# phase.net
KiCad netlist of a schematic drawn in Altium Designer
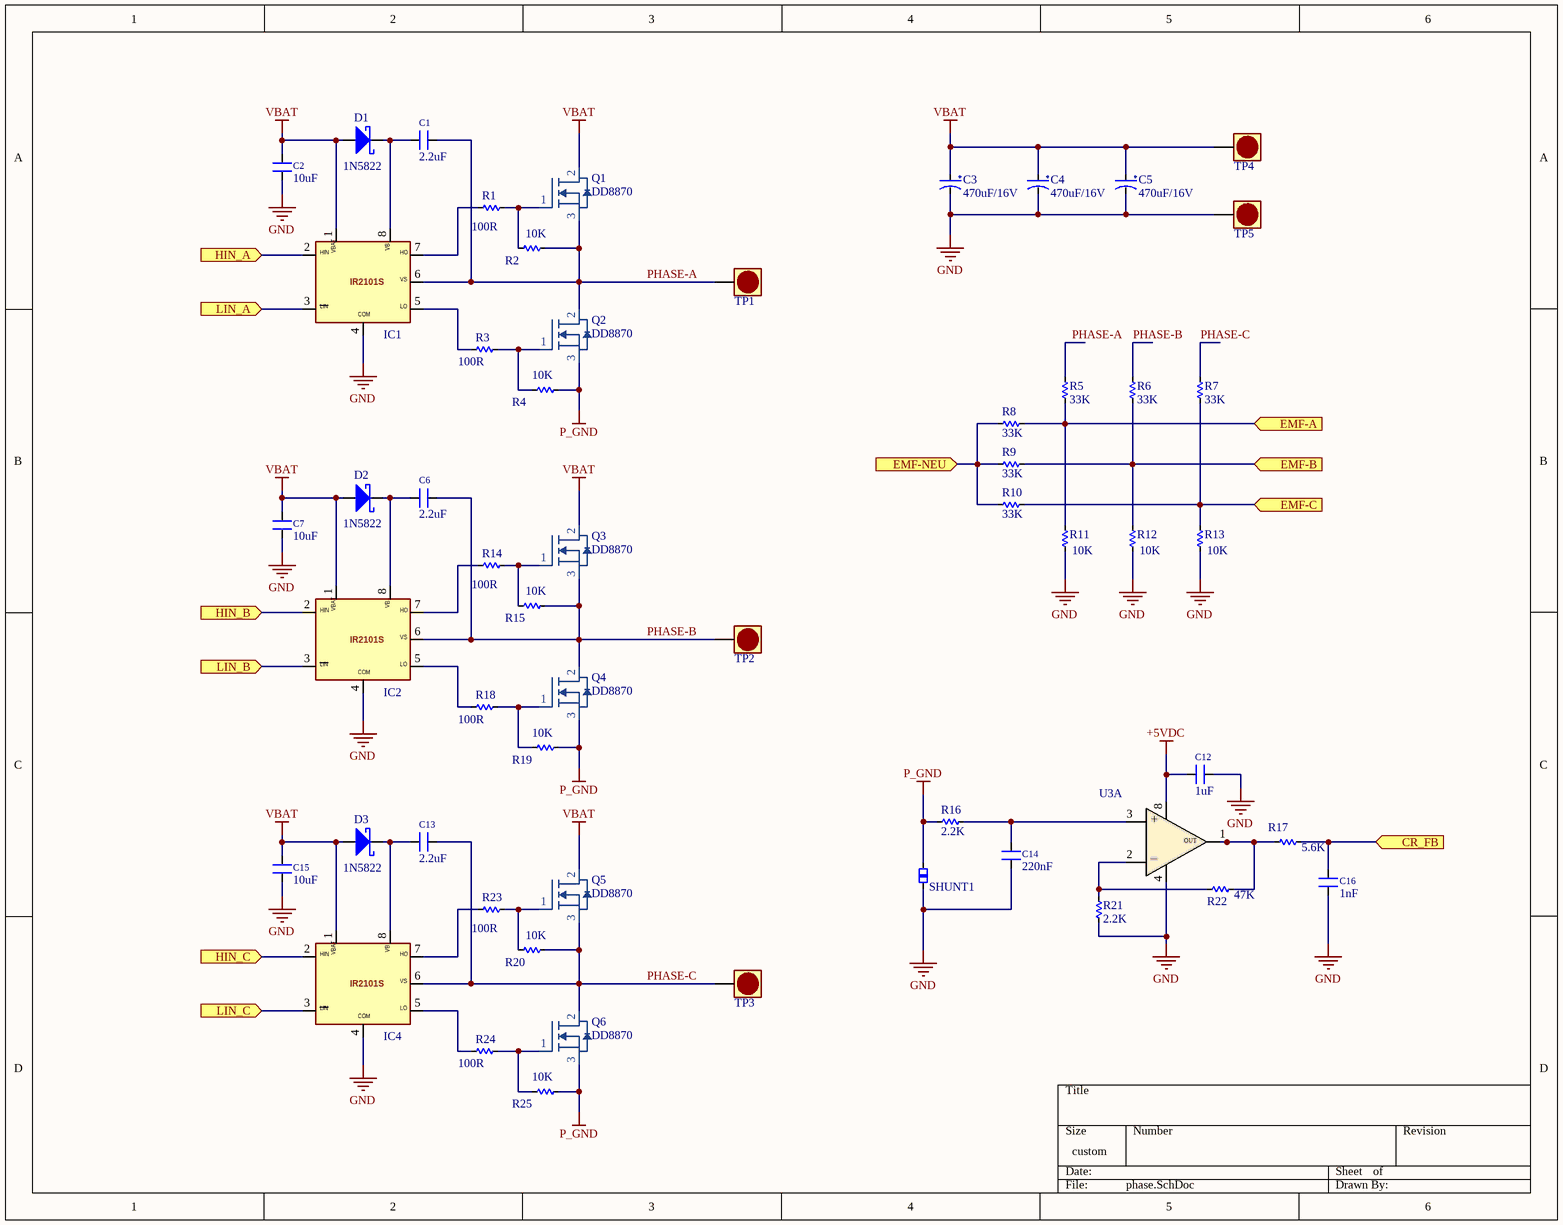
[diagram p0: phase.SchDoc]

(export (version "E")
  (design (tool "Eeschema 10.0.6"))
  (components
    (comp (ref "C1")
      (value "2.2uF")
      (footprint "CN-SMD-0805")
      (description "CAP SMD")
      (fields (field (name "DESIGNED BY") "VanDungEvn"))
      (libsource (lib "Sang_Library") (part "CAP SMD"))
    )
    (comp (ref "C2")
      (value "10uF")
      (footprint "SM-CAP-0805")
      (description "CAP SMD")
      (fields (field (name "DESIGNED BY") "VanDungEvn"))
      (libsource (lib "Sang_Library") (part "CAP SMD"))
    )
    (comp (ref "C3")
      (value "470uF/16V")
      (footprint "CAP-ALU-SMD-F")
      (description "CAP-ALU-SMD")
      (fields (field (name "PUBLISHER") "Altium Limited"))
      (libsource (lib "Sang_Library") (part "CAP-ALU-SMD"))
    )
    (comp (ref "C4")
      (value "470uF/16V")
      (footprint "CAP-ALU-SMD-F")
      (description "CAP-ALU-SMD")
      (fields (field (name "PUBLISHER") "Altium Limited"))
      (libsource (lib "Sang_Library") (part "CAP-ALU-SMD"))
    )
    (comp (ref "C5")
      (value "470uF/16V")
      (footprint "CAP-ALU-SMD-F")
      (description "CAP-ALU-SMD")
      (fields (field (name "PUBLISHER") "Altium Limited"))
      (libsource (lib "Sang_Library") (part "CAP-ALU-SMD"))
    )
    (comp (ref "C6")
      (value "2.2uF")
      (footprint "CN-SMD-0805")
      (description "CAP SMD")
      (fields (field (name "DESIGNED BY") "VanDungEvn"))
      (libsource (lib "Sang_Library") (part "CAP SMD"))
    )
    (comp (ref "C7")
      (value "10uF")
      (footprint "SM-CAP-0805")
      (description "CAP SMD")
      (fields (field (name "DESIGNED BY") "VanDungEvn"))
      (libsource (lib "Sang_Library") (part "CAP SMD"))
    )
    (comp (ref "C12")
      (value "1uF")
      (footprint "CN-SMD-0805")
      (description "CAP SMD")
      (fields (field (name "DESIGNED BY") "VanDungEvn"))
      (libsource (lib "Sang_Library") (part "CAP SMD"))
    )
    (comp (ref "C13")
      (value "2.2uF")
      (footprint "CN-SMD-0805")
      (description "CAP SMD")
      (fields (field (name "DESIGNED BY") "VanDungEvn"))
      (libsource (lib "Sang_Library") (part "CAP SMD"))
    )
    (comp (ref "C14")
      (value "220nF")
      (footprint "CN-SMD-0805")
      (description "CAP SMD")
      (fields (field (name "DESIGNED BY") "VanDungEvn"))
      (libsource (lib "Sang_Library") (part "CAP SMD"))
    )
    (comp (ref "C15")
      (value "10uF")
      (footprint "SM-CAP-0805")
      (description "CAP SMD")
      (fields (field (name "DESIGNED BY") "VanDungEvn"))
      (libsource (lib "Sang_Library") (part "CAP SMD"))
    )
    (comp (ref "C16")
      (value "1nF")
      (footprint "CN-SMD-0805")
      (description "CAP SMD")
      (fields (field (name "DESIGNED BY") "VanDungEvn"))
      (libsource (lib "Sang_Library") (part "CAP SMD"))
    )
    (comp (ref "D1")
      (value "1N5822")
      (footprint "DO-214AC")
      (description "Diode Schottky")
      (fields (field (name "PART NUMBER") "LED 3 ly Single Colour"))
      (libsource (lib "KhanhBK_Library_4") (part "Diode Schottky"))
    )
    (comp (ref "D2")
      (value "1N5822")
      (footprint "DO-214AC")
      (description "Diode Schottky")
      (fields (field (name "PART NUMBER") "LED 3 ly Single Colour"))
      (libsource (lib "KhanhBK_Library_4") (part "Diode Schottky"))
    )
    (comp (ref "D3")
      (value "1N5822")
      (footprint "DO-214AC")
      (description "Diode Schottky")
      (fields (field (name "PART NUMBER") "LED 3 ly Single Colour"))
      (libsource (lib "KhanhBK_Library_4") (part "Diode Schottky"))
    )
    (comp (ref "IC1") (value "IR2101S") (footprint "SOIC-8") (libsource (lib "Huan") (part "IR2101S")))
    (comp (ref "IC2") (value "IR2101S") (footprint "SOIC-8") (libsource (lib "Huan") (part "IR2101S")))
    (comp (ref "IC4") (value "IR2101S") (footprint "SOIC-8") (libsource (lib "Huan") (part "IR2101S")))
    (comp (ref "Q1")
      (value "DD8870")
      (footprint "TO-252")
      (description "MOSFET N chane")
      (libsource (lib "Huan") (part "MOSFET-N"))
    )
    (comp (ref "Q2")
      (value "DD8870")
      (footprint "TO-252")
      (description "MOSFET N chane")
      (libsource (lib "Huan") (part "MOSFET-N"))
    )
    (comp (ref "Q3")
      (value "DD8870")
      (footprint "TO-252")
      (description "MOSFET N chane")
      (libsource (lib "Huan") (part "MOSFET-N"))
    )
    (comp (ref "Q4")
      (value "DD8870")
      (footprint "TO-252")
      (description "MOSFET N chane")
      (libsource (lib "Huan") (part "MOSFET-N"))
    )
    (comp (ref "Q5")
      (value "DD8870")
      (footprint "TO-252")
      (description "MOSFET N chane")
      (libsource (lib "Huan") (part "MOSFET-N"))
    )
    (comp (ref "Q6")
      (value "DD8870")
      (footprint "TO-252")
      (description "MOSFET N chane")
      (libsource (lib "Huan") (part "MOSFET-N"))
    )
    (comp (ref "R1")
      (value "100R")
      (footprint "RES-SMD-0805")
      (description "Resistor")
      (fields
        (field (name "MANUFACTURER") "Generic Components")
        (field (name "PUBLISHER") "Altium Hobart Technology Centre")
      )
      (libsource (lib "Sang_Library") (part "Res-SMD"))
    )
    (comp (ref "R2")
      (value "10K")
      (footprint "RES-SMD-0805")
      (description "Resistor")
      (fields
        (field (name "MANUFACTURER") "Generic Components")
        (field (name "PUBLISHER") "Altium Hobart Technology Centre")
      )
      (libsource (lib "Sang_Library") (part "Res-SMD"))
    )
    (comp (ref "R3")
      (value "100R")
      (footprint "RES-SMD-0805")
      (description "Resistor")
      (fields
        (field (name "MANUFACTURER") "Generic Components")
        (field (name "PUBLISHER") "Altium Hobart Technology Centre")
      )
      (libsource (lib "Sang_Library") (part "Res-SMD"))
    )
    (comp (ref "R4")
      (value "10K")
      (footprint "RES-SMD-0805")
      (description "Resistor")
      (fields
        (field (name "MANUFACTURER") "Generic Components")
        (field (name "PUBLISHER") "Altium Hobart Technology Centre")
      )
      (libsource (lib "Sang_Library") (part "Res-SMD"))
    )
    (comp (ref "R5")
      (value "33K")
      (footprint "RES-SMD-0603")
      (description "Resistor")
      (fields
        (field (name "MANUFACTURER") "Generic Components")
        (field (name "PUBLISHER") "Altium Hobart Technology Centre")
      )
      (libsource (lib "Sang_Library") (part "Res-SMD"))
    )
    (comp (ref "R6")
      (value "33K")
      (footprint "RES-SMD-0603")
      (description "Resistor")
      (fields
        (field (name "MANUFACTURER") "Generic Components")
        (field (name "PUBLISHER") "Altium Hobart Technology Centre")
      )
      (libsource (lib "Sang_Library") (part "Res-SMD"))
    )
    (comp (ref "R7")
      (value "33K")
      (footprint "RES-SMD-0603")
      (description "Resistor")
      (fields
        (field (name "MANUFACTURER") "Generic Components")
        (field (name "PUBLISHER") "Altium Hobart Technology Centre")
      )
      (libsource (lib "Sang_Library") (part "Res-SMD"))
    )
    (comp (ref "R8")
      (value "33K")
      (footprint "RES-SMD-0603")
      (description "Resistor")
      (fields
        (field (name "MANUFACTURER") "Generic Components")
        (field (name "PUBLISHER") "Altium Hobart Technology Centre")
      )
      (libsource (lib "Sang_Library") (part "Res-SMD"))
    )
    (comp (ref "R9")
      (value "33K")
      (footprint "RES-SMD-0603")
      (description "Resistor")
      (fields
        (field (name "MANUFACTURER") "Generic Components")
        (field (name "PUBLISHER") "Altium Hobart Technology Centre")
      )
      (libsource (lib "Sang_Library") (part "Res-SMD"))
    )
    (comp (ref "R10")
      (value "33K")
      (footprint "RES-SMD-0603")
      (description "Resistor")
      (fields
        (field (name "MANUFACTURER") "Generic Components")
        (field (name "PUBLISHER") "Altium Hobart Technology Centre")
      )
      (libsource (lib "Sang_Library") (part "Res-SMD"))
    )
    (comp (ref "R11")
      (value "10K")
      (footprint "RES-SMD-0603")
      (description "Resistor")
      (fields
        (field (name "MANUFACTURER") "Generic Components")
        (field (name "PUBLISHER") "Altium Hobart Technology Centre")
      )
      (libsource (lib "Sang_Library") (part "Res-SMD"))
    )
    (comp (ref "R12")
      (value "10K")
      (footprint "RES-SMD-0603")
      (description "Resistor")
      (fields
        (field (name "MANUFACTURER") "Generic Components")
        (field (name "PUBLISHER") "Altium Hobart Technology Centre")
      )
      (libsource (lib "Sang_Library") (part "Res-SMD"))
    )
    (comp (ref "R13")
      (value "10K")
      (footprint "RES-SMD-0603")
      (description "Resistor")
      (fields
        (field (name "MANUFACTURER") "Generic Components")
        (field (name "PUBLISHER") "Altium Hobart Technology Centre")
      )
      (libsource (lib "Sang_Library") (part "Res-SMD"))
    )
    (comp (ref "R14")
      (value "100R")
      (footprint "RES-SMD-0805")
      (description "Resistor")
      (fields
        (field (name "MANUFACTURER") "Generic Components")
        (field (name "PUBLISHER") "Altium Hobart Technology Centre")
      )
      (libsource (lib "Sang_Library") (part "Res-SMD"))
    )
    (comp (ref "R15")
      (value "10K")
      (footprint "RES-SMD-0805")
      (description "Resistor")
      (fields
        (field (name "MANUFACTURER") "Generic Components")
        (field (name "PUBLISHER") "Altium Hobart Technology Centre")
      )
      (libsource (lib "Sang_Library") (part "Res-SMD"))
    )
    (comp (ref "R16")
      (value "2.2K")
      (footprint "RES-SMD-0805")
      (description "Resistor")
      (fields
        (field (name "MANUFACTURER") "Generic Components")
        (field (name "PUBLISHER") "Altium Hobart Technology Centre")
      )
      (libsource (lib "Sang_Library") (part "Res-SMD"))
    )
    (comp (ref "R17")
      (value "5.6K")
      (footprint "RES-SMD-0805")
      (description "Resistor")
      (fields
        (field (name "MANUFACTURER") "Generic Components")
        (field (name "PUBLISHER") "Altium Hobart Technology Centre")
      )
      (libsource (lib "Sang_Library") (part "Res-SMD"))
    )
    (comp (ref "R18")
      (value "100R")
      (footprint "RES-SMD-0805")
      (description "Resistor")
      (fields
        (field (name "MANUFACTURER") "Generic Components")
        (field (name "PUBLISHER") "Altium Hobart Technology Centre")
      )
      (libsource (lib "Sang_Library") (part "Res-SMD"))
    )
    (comp (ref "R19")
      (value "10K")
      (footprint "RES-SMD-0805")
      (description "Resistor")
      (fields
        (field (name "MANUFACTURER") "Generic Components")
        (field (name "PUBLISHER") "Altium Hobart Technology Centre")
      )
      (libsource (lib "Sang_Library") (part "Res-SMD"))
    )
    (comp (ref "R20")
      (value "10K")
      (footprint "RES-SMD-0805")
      (description "Resistor")
      (fields
        (field (name "MANUFACTURER") "Generic Components")
        (field (name "PUBLISHER") "Altium Hobart Technology Centre")
      )
      (libsource (lib "Sang_Library") (part "Res-SMD"))
    )
    (comp (ref "R21")
      (value "2.2K")
      (footprint "RES-SMD-0805")
      (description "Resistor")
      (fields
        (field (name "MANUFACTURER") "Generic Components")
        (field (name "PUBLISHER") "Altium Hobart Technology Centre")
      )
      (libsource (lib "Sang_Library") (part "Res-SMD"))
    )
    (comp (ref "R22")
      (value "47K")
      (footprint "RES-SMD-0805")
      (description "Resistor")
      (fields
        (field (name "MANUFACTURER") "Generic Components")
        (field (name "PUBLISHER") "Altium Hobart Technology Centre")
      )
      (libsource (lib "Sang_Library") (part "Res-SMD"))
    )
    (comp (ref "R23")
      (value "100R")
      (footprint "RES-SMD-0805")
      (description "Resistor")
      (fields
        (field (name "MANUFACTURER") "Generic Components")
        (field (name "PUBLISHER") "Altium Hobart Technology Centre")
      )
      (libsource (lib "Sang_Library") (part "Res-SMD"))
    )
    (comp (ref "R24")
      (value "100R")
      (footprint "RES-SMD-0805")
      (description "Resistor")
      (fields
        (field (name "MANUFACTURER") "Generic Components")
        (field (name "PUBLISHER") "Altium Hobart Technology Centre")
      )
      (libsource (lib "Sang_Library") (part "Res-SMD"))
    )
    (comp (ref "R25")
      (value "10K")
      (footprint "RES-SMD-0805")
      (description "Resistor")
      (fields
        (field (name "MANUFACTURER") "Generic Components")
        (field (name "PUBLISHER") "Altium Hobart Technology Centre")
      )
      (libsource (lib "Sang_Library") (part "Res-SMD"))
    )
    (comp (ref "SHUNT1") (value "Shunt") (footprint "SHUNT10MM") (libsource (lib "Huan") (part "Shunt")))
    (comp (ref "TP1") (value "JP1P") (footprint "PW-JP") (libsource (lib "Huan") (part "JP1P")))
    (comp (ref "TP2") (value "JP1P") (footprint "PW-JP") (libsource (lib "Huan") (part "JP1P")))
    (comp (ref "TP3") (value "JP1P") (footprint "PW-JP") (libsource (lib "Huan") (part "JP1P")))
    (comp (ref "TP4") (value "JP1P") (footprint "PW-JP") (libsource (lib "Huan") (part "JP1P")))
    (comp (ref "TP5") (value "JP1P") (footprint "PW-JP") (libsource (lib "Huan") (part "JP1P")))
    (comp (ref "U3") (value "MCP6002") (footprint "DIP-8") (libsource (lib "Huan") (part "MCP6002")))
  )
  (nets
    (net (code "1") (name "+5VDC") (class "Default")
      (node (ref "C12") (pin "1") (pinfunction "1_1") (pintype "passive"))
      (node (ref "U3") (pin "8") (pinfunction "8_8") (pintype "passive"))
    )
    (net (code "2") (name "/CR_FB") (class "Default")
      (node (ref "C16") (pin "1") (pinfunction "1_1") (pintype "passive"))
      (node (ref "R17") (pin "2") (pinfunction "2_2") (pintype "passive"))
    )
    (net (code "3") (name "/EMF-A") (class "Default")
      (node (ref "R11") (pin "1") (pinfunction "1_1") (pintype "passive"))
      (node (ref "R5") (pin "2") (pinfunction "2_2") (pintype "passive"))
      (node (ref "R8") (pin "2") (pinfunction "2_2") (pintype "passive"))
    )
    (net (code "4") (name "/EMF-B") (class "Default")
      (node (ref "R12") (pin "1") (pinfunction "1_1") (pintype "passive"))
      (node (ref "R6") (pin "2") (pinfunction "2_2") (pintype "passive"))
      (node (ref "R9") (pin "2") (pinfunction "2_2") (pintype "passive"))
    )
    (net (code "5") (name "/EMF-C") (class "Default")
      (node (ref "R10") (pin "2") (pinfunction "2_2") (pintype "passive"))
      (node (ref "R13") (pin "1") (pinfunction "1_1") (pintype "passive"))
      (node (ref "R7") (pin "2") (pinfunction "2_2") (pintype "passive"))
    )
    (net (code "6") (name "/EMF-NEU") (class "Default")
      (node (ref "R10") (pin "1") (pinfunction "1_1") (pintype "passive"))
      (node (ref "R8") (pin "1") (pinfunction "1_1") (pintype "passive"))
      (node (ref "R9") (pin "1") (pinfunction "1_1") (pintype "passive"))
    )
    (net (code "7") (name "/HIN_A") (class "Default")
      (node (ref "IC1") (pin "2") (pinfunction "2_2") (pintype "passive"))
    )
    (net (code "8") (name "/HIN_B") (class "Default")
      (node (ref "IC2") (pin "2") (pinfunction "2_2") (pintype "passive"))
    )
    (net (code "9") (name "/HIN_C") (class "Default")
      (node (ref "IC4") (pin "2") (pinfunction "2_2") (pintype "passive"))
    )
    (net (code "10") (name "/LIN_A") (class "Default")
      (node (ref "IC1") (pin "3") (pinfunction "3_3") (pintype "passive"))
    )
    (net (code "11") (name "/LIN_B") (class "Default")
      (node (ref "IC2") (pin "3") (pinfunction "3_3") (pintype "passive"))
    )
    (net (code "12") (name "/LIN_C") (class "Default")
      (node (ref "IC4") (pin "3") (pinfunction "3_3") (pintype "passive"))
    )
    (net (code "13") (name "/PHASE-A") (class "Default")
      (node (ref "C1") (pin "2") (pinfunction "2_2") (pintype "passive"))
      (node (ref "IC1") (pin "6") (pinfunction "6_6") (pintype "passive"))
      (node (ref "Q1") (pin "3") (pinfunction "3_3") (pintype "passive"))
      (node (ref "Q2") (pin "2") (pinfunction "2_2") (pintype "passive"))
      (node (ref "R2") (pin "2") (pinfunction "2_2") (pintype "passive"))
      (node (ref "R5") (pin "1") (pinfunction "1_1") (pintype "passive"))
      (node (ref "TP1") (pin "1") (pinfunction "1_1") (pintype "passive"))
    )
    (net (code "14") (name "/PHASE-B") (class "Default")
      (node (ref "C6") (pin "2") (pinfunction "2_2") (pintype "passive"))
      (node (ref "IC2") (pin "6") (pinfunction "6_6") (pintype "passive"))
      (node (ref "Q3") (pin "3") (pinfunction "3_3") (pintype "passive"))
      (node (ref "Q4") (pin "2") (pinfunction "2_2") (pintype "passive"))
      (node (ref "R15") (pin "2") (pinfunction "2_2") (pintype "passive"))
      (node (ref "R6") (pin "1") (pinfunction "1_1") (pintype "passive"))
      (node (ref "TP2") (pin "1") (pinfunction "1_1") (pintype "passive"))
    )
    (net (code "15") (name "/PHASE-C") (class "Default")
      (node (ref "C13") (pin "2") (pinfunction "2_2") (pintype "passive"))
      (node (ref "IC4") (pin "6") (pinfunction "6_6") (pintype "passive"))
      (node (ref "Q5") (pin "3") (pinfunction "3_3") (pintype "passive"))
      (node (ref "Q6") (pin "2") (pinfunction "2_2") (pintype "passive"))
      (node (ref "R20") (pin "2") (pinfunction "2_2") (pintype "passive"))
      (node (ref "R7") (pin "1") (pinfunction "1_1") (pintype "passive"))
      (node (ref "TP3") (pin "1") (pinfunction "1_1") (pintype "passive"))
    )
    (net (code "16") (name "GND") (class "Default")
      (node (ref "C12") (pin "2") (pinfunction "2_2") (pintype "passive"))
      (node (ref "C14") (pin "1") (pinfunction "1_1") (pintype "passive"))
      (node (ref "C15") (pin "1") (pinfunction "1_1") (pintype "passive"))
      (node (ref "C16") (pin "2") (pinfunction "2_2") (pintype "passive"))
      (node (ref "C2") (pin "1") (pinfunction "1_1") (pintype "passive"))
      (node (ref "C3") (pin "2") (pinfunction "2_2") (pintype "passive"))
      (node (ref "C4") (pin "2") (pinfunction "2_2") (pintype "passive"))
      (node (ref "C5") (pin "2") (pinfunction "2_2") (pintype "passive"))
      (node (ref "C7") (pin "1") (pinfunction "1_1") (pintype "passive"))
      (node (ref "IC1") (pin "4") (pinfunction "4_4") (pintype "passive"))
      (node (ref "IC2") (pin "4") (pinfunction "4_4") (pintype "passive"))
      (node (ref "IC4") (pin "4") (pinfunction "4_4") (pintype "passive"))
      (node (ref "R11") (pin "2") (pinfunction "2_2") (pintype "passive"))
      (node (ref "R12") (pin "2") (pinfunction "2_2") (pintype "passive"))
      (node (ref "R13") (pin "2") (pinfunction "2_2") (pintype "passive"))
      (node (ref "R21") (pin "1") (pinfunction "1_1") (pintype "passive"))
      (node (ref "SHUNT1") (pin "1") (pinfunction "1_1") (pintype "passive"))
      (node (ref "TP5") (pin "1") (pinfunction "1_1") (pintype "passive"))
      (node (ref "U3") (pin "4") (pinfunction "4_4") (pintype "passive"))
    )
    (net (code "17") (name "Net-(C1-Pad1)") (class "Default")
      (node (ref "C1") (pin "1") (pinfunction "1_1") (pintype "passive"))
      (node (ref "D1") (pin "2") (pinfunction "2_2") (pintype "passive"))
      (node (ref "IC1") (pin "8") (pinfunction "8_8") (pintype "passive"))
    )
    (net (code "18") (name "Net-(C6-Pad1)") (class "Default")
      (node (ref "C6") (pin "1") (pinfunction "1_1") (pintype "passive"))
      (node (ref "D2") (pin "2") (pinfunction "2_2") (pintype "passive"))
      (node (ref "IC2") (pin "8") (pinfunction "8_8") (pintype "passive"))
    )
    (net (code "19") (name "Net-(C13-Pad1)") (class "Default")
      (node (ref "C13") (pin "1") (pinfunction "1_1") (pintype "passive"))
      (node (ref "D3") (pin "2") (pinfunction "2_2") (pintype "passive"))
      (node (ref "IC4") (pin "8") (pinfunction "8_8") (pintype "passive"))
    )
    (net (code "20") (name "Net-(C14-Pad2)") (class "Default")
      (node (ref "C14") (pin "2") (pinfunction "2_2") (pintype "passive"))
      (node (ref "R16") (pin "2") (pinfunction "2_2") (pintype "passive"))
      (node (ref "U3") (pin "3") (pinfunction "3_3") (pintype "passive"))
    )
    (net (code "21") (name "Net-(IC1-Pad5)") (class "Default")
      (node (ref "IC1") (pin "5") (pinfunction "5_5") (pintype "passive"))
      (node (ref "R3") (pin "2") (pinfunction "2_2") (pintype "passive"))
    )
    (net (code "22") (name "Net-(IC1-Pad7)") (class "Default")
      (node (ref "IC1") (pin "7") (pinfunction "7_7") (pintype "passive"))
      (node (ref "R1") (pin "2") (pinfunction "2_2") (pintype "passive"))
    )
    (net (code "23") (name "Net-(IC2-Pad5)") (class "Default")
      (node (ref "IC2") (pin "5") (pinfunction "5_5") (pintype "passive"))
      (node (ref "R18") (pin "2") (pinfunction "2_2") (pintype "passive"))
    )
    (net (code "24") (name "Net-(IC2-Pad7)") (class "Default")
      (node (ref "IC2") (pin "7") (pinfunction "7_7") (pintype "passive"))
      (node (ref "R14") (pin "2") (pinfunction "2_2") (pintype "passive"))
    )
    (net (code "25") (name "Net-(IC4-Pad5)") (class "Default")
      (node (ref "IC4") (pin "5") (pinfunction "5_5") (pintype "passive"))
      (node (ref "R24") (pin "2") (pinfunction "2_2") (pintype "passive"))
    )
    (net (code "26") (name "Net-(IC4-Pad7)") (class "Default")
      (node (ref "IC4") (pin "7") (pinfunction "7_7") (pintype "passive"))
      (node (ref "R23") (pin "2") (pinfunction "2_2") (pintype "passive"))
    )
    (net (code "27") (name "Net-(Q1-Pad1)") (class "Default")
      (node (ref "Q1") (pin "1") (pinfunction "1_1") (pintype "passive"))
      (node (ref "R1") (pin "1") (pinfunction "1_1") (pintype "passive"))
      (node (ref "R2") (pin "1") (pinfunction "1_1") (pintype "passive"))
    )
    (net (code "28") (name "Net-(Q2-Pad1)") (class "Default")
      (node (ref "Q2") (pin "1") (pinfunction "1_1") (pintype "passive"))
      (node (ref "R3") (pin "1") (pinfunction "1_1") (pintype "passive"))
      (node (ref "R4") (pin "1") (pinfunction "1_1") (pintype "passive"))
    )
    (net (code "29") (name "Net-(Q3-Pad1)") (class "Default")
      (node (ref "Q3") (pin "1") (pinfunction "1_1") (pintype "passive"))
      (node (ref "R14") (pin "1") (pinfunction "1_1") (pintype "passive"))
      (node (ref "R15") (pin "1") (pinfunction "1_1") (pintype "passive"))
    )
    (net (code "30") (name "Net-(Q4-Pad1)") (class "Default")
      (node (ref "Q4") (pin "1") (pinfunction "1_1") (pintype "passive"))
      (node (ref "R18") (pin "1") (pinfunction "1_1") (pintype "passive"))
      (node (ref "R19") (pin "1") (pinfunction "1_1") (pintype "passive"))
    )
    (net (code "31") (name "Net-(Q5-Pad1)") (class "Default")
      (node (ref "Q5") (pin "1") (pinfunction "1_1") (pintype "passive"))
      (node (ref "R20") (pin "1") (pinfunction "1_1") (pintype "passive"))
      (node (ref "R23") (pin "1") (pinfunction "1_1") (pintype "passive"))
    )
    (net (code "32") (name "Net-(Q6-Pad1)") (class "Default")
      (node (ref "Q6") (pin "1") (pinfunction "1_1") (pintype "passive"))
      (node (ref "R24") (pin "1") (pinfunction "1_1") (pintype "passive"))
      (node (ref "R25") (pin "1") (pinfunction "1_1") (pintype "passive"))
    )
    (net (code "33") (name "Net-(R17-Pad1)") (class "Default")
      (node (ref "R17") (pin "1") (pinfunction "1_1") (pintype "passive"))
      (node (ref "R22") (pin "2") (pinfunction "2_2") (pintype "passive"))
      (node (ref "U3") (pin "1") (pinfunction "1_1") (pintype "passive"))
    )
    (net (code "34") (name "Net-(R21-Pad2)") (class "Default")
      (node (ref "R21") (pin "2") (pinfunction "2_2") (pintype "passive"))
      (node (ref "R22") (pin "1") (pinfunction "1_1") (pintype "passive"))
      (node (ref "U3") (pin "2") (pintype "passive"))
    )
    (net (code "35") (name "P_GND") (class "Default")
      (node (ref "Q2") (pin "3") (pinfunction "3_3") (pintype "passive"))
      (node (ref "Q4") (pin "3") (pinfunction "3_3") (pintype "passive"))
      (node (ref "Q6") (pin "3") (pinfunction "3_3") (pintype "passive"))
      (node (ref "R16") (pin "1") (pinfunction "1_1") (pintype "passive"))
      (node (ref "R19") (pin "2") (pinfunction "2_2") (pintype "passive"))
      (node (ref "R25") (pin "2") (pinfunction "2_2") (pintype "passive"))
      (node (ref "R4") (pin "2") (pinfunction "2_2") (pintype "passive"))
      (node (ref "SHUNT1") (pin "2") (pinfunction "2_2") (pintype "passive"))
    )
    (net (code "36") (name "VBAT") (class "Default")
      (node (ref "C15") (pin "2") (pinfunction "2_2") (pintype "passive"))
      (node (ref "C2") (pin "2") (pinfunction "2_2") (pintype "passive"))
      (node (ref "C3") (pin "1") (pinfunction "1_1") (pintype "passive"))
      (node (ref "C4") (pin "1") (pinfunction "1_1") (pintype "passive"))
      (node (ref "C5") (pin "1") (pinfunction "1_1") (pintype "passive"))
      (node (ref "C7") (pin "2") (pinfunction "2_2") (pintype "passive"))
      (node (ref "D1") (pin "1") (pinfunction "1_1") (pintype "passive"))
      (node (ref "D2") (pin "1") (pinfunction "1_1") (pintype "passive"))
      (node (ref "D3") (pin "1") (pinfunction "1_1") (pintype "passive"))
      (node (ref "IC1") (pin "1") (pinfunction "1_1") (pintype "passive"))
      (node (ref "IC2") (pin "1") (pinfunction "1_1") (pintype "passive"))
      (node (ref "IC4") (pin "1") (pinfunction "1_1") (pintype "passive"))
      (node (ref "Q1") (pin "2") (pinfunction "2_2") (pintype "passive"))
      (node (ref "Q3") (pin "2") (pinfunction "2_2") (pintype "passive"))
      (node (ref "Q5") (pin "2") (pinfunction "2_2") (pintype "passive"))
      (node (ref "TP4") (pin "1") (pinfunction "1_1") (pintype "passive"))
    )
  )
)
